# dcdc_60v_12v.net
KiCad netlist of a schematic drawn in Altium Designer
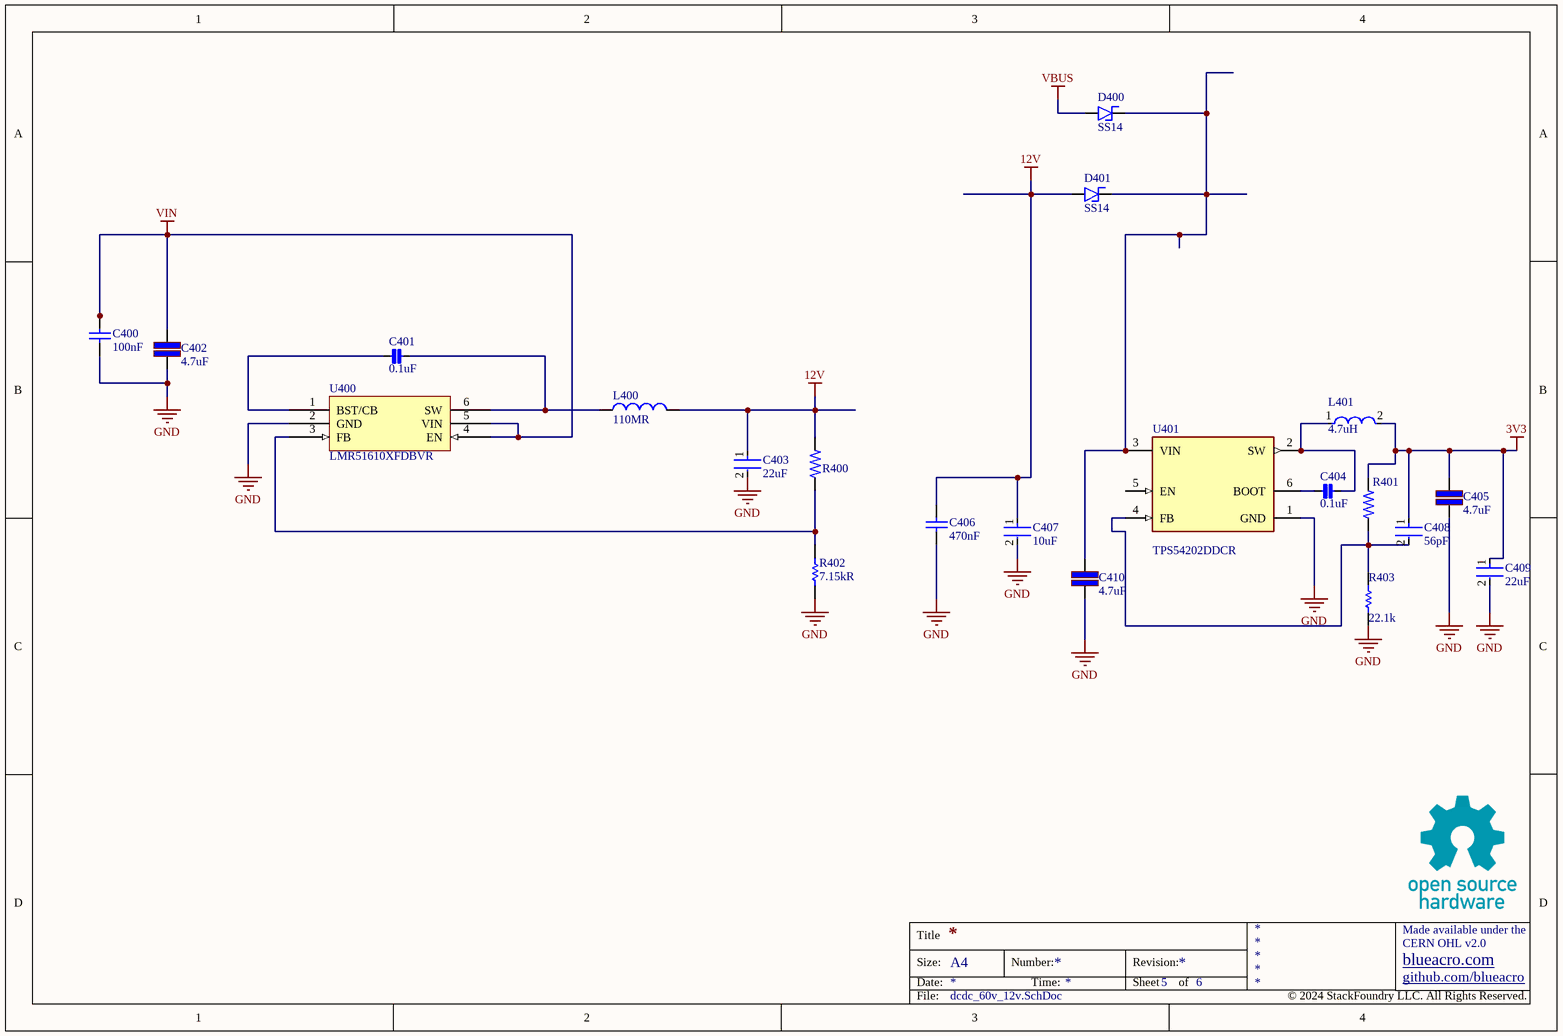
[diagram p0: dcdc_60v_12v.SchDoc]

(export (version "E")
  (design (tool "Eeschema 10.0.6"))
  (components
    (comp (ref "C400")
      (value "100nF")
      (footprint "CAPC2013X94X50ML20T25")
      (fields (field (name "Comment") "0.1uF X7R 100V 0805"))
      (libsource (lib "StackFoundry LLC") (part "CAP"))
    )
    (comp (ref "C401")
      (value "0.1uF")
      (footprint "FP-CL10-IPC_B")
      (description "Cap Ceramic 0.1uF 50V X7R 20% SMD 0603 125C Paper T/R")
      (fields (field (name "VOLTAGE") "50V") (field (name "Comment") "CAP 0.1uF 50V X7R 0603"))
      (libsource (lib "StackFoundry LLC") (part "C-EU"))
    )
    (comp (ref "C402")
      (value "4.7uF")
      (footprint "CAPC3225X20N")
      (description "CAP CER 4.7UF 50V X7R 1210")
      (fields (field (name "VOLTAGE") "50V") (field (name "TOLERANCE") "10%"))
      (libsource (lib "StackFoundry LLC") (part "4.7uF"))
    )
    (comp (ref "C403")
      (value "22uF")
      (footprint "FP-1210-L_3_2_0_3-W_2_5_0-MFG")
      (description "1210 22 uF 25 V ±20% Tolerance X7R Multilayer Ceramic Chip Capacitor")
      (fields (field (name "TOLERANCE") "20%") (field (name "Comment") "CAP 22uF 25V 1210 X7R"))
      (libsource (lib "StackFoundry LLC") (part "02cd4be3c70576c341d710602a673aa"))
    )
    (comp (ref "C404")
      (value "0.1uF")
      (footprint "FP-CL10-IPC_B")
      (description "Cap Ceramic 0.1uF 50V X7R 20% SMD 0603 125C Paper T/R")
      (fields (field (name "VOLTAGE") "50V") (field (name "Comment") "CAP 0.1uF 50V X7R 0603"))
      (libsource (lib "StackFoundry LLC") (part "C-EU"))
    )
    (comp (ref "C405")
      (value "4.7uF")
      (footprint "CAPC3225X20N")
      (description "CAP CER 4.7UF 50V X7R 1210")
      (fields (field (name "VOLTAGE") "50V") (field (name "TOLERANCE") "10%"))
      (libsource (lib "StackFoundry LLC") (part "4.7uF"))
    )
    (comp (ref "C406")
      (value "470nF")
      (footprint "CAPC1210(3225)230_M")
      (description "Multilayer Ceramic Capacitor, 0.47 uF, 50 V, ± 10%, X7R, 1210 [3225 Metric]")
      (fields (field (name "TOLERANCE") "10%") (field (name "VOLTAGE") "50V"))
      (libsource (lib "StackFoundry LLC") (part "CAP"))
    )
    (comp (ref "C407")
      (value "10uF")
      (footprint "FP-GRM32E-0_2-0_3-MFG")
      (description "Multilayer Ceramic Capacitors MLCC - SMD/SMT 1210 10uF 63volts *Derate Voltage/Temp")
      (fields (field (name "TOLERANCE") "10%") (field (name "VOLTAGE") "63V"))
      (libsource (lib "StackFoundry LLC") (part "11868f565c42a9108669ba33697ecf6"))
    )
    (comp (ref "C408")
      (value "56pF")
      (footprint "FP-C0603C-CF-IPC_B")
      (description "Multilayer Ceramic Capacitor, 56 pF, 50 V, ± 5%, C0G (NP0), 0603 [1608 Metric]")
      (fields (field (name "TOLERANCE") "5%") (field (name "Comment") "C0603C560J5GACTU"))
      (libsource (lib "StackFoundry LLC") (part "b4654b650e69147ec39a6b967a45e02"))
    )
    (comp (ref "C409")
      (value "22uF")
      (footprint "FP-1210-L_3_2_0_3-W_2_5_0-MFG")
      (description "1210 22 uF 25 V ±20% Tolerance X7R Multilayer Ceramic Chip Capacitor")
      (fields (field (name "TOLERANCE") "20%") (field (name "Comment") "CAP 22uF 25V 1210 X7R"))
      (libsource (lib "StackFoundry LLC") (part "02cd4be3c70576c341d710602a673aa"))
    )
    (comp (ref "C410")
      (value "4.7uF")
      (footprint "CAPC3225X20N")
      (description "CAP CER 4.7UF 50V X7R 1210")
      (fields (field (name "VOLTAGE") "50V") (field (name "TOLERANCE") "10%"))
      (libsource (lib "StackFoundry LLC") (part "4.7uF"))
    )
    (comp (ref "D400")
      (value "SS14")
      (footprint "SMA")
      (libsource (lib "StackFoundry LLC") (part "DIODE_SCHOTTKY"))
    )
    (comp (ref "D401")
      (value "SS14")
      (footprint "SMA")
      (libsource (lib "StackFoundry LLC") (part "DIODE_SCHOTTKY"))
    )
    (comp (ref "L400")
      (value "110MR")
      (footprint "SRR1260-680M-Footprint-1")
      (description "Ind Power Shielded Wirewound 68uH 20% 100KHz 22Q-Factor Ferrite 2.1A T/R")
      (fields (field (name "TOLERANCE") "20%") (field (name "Comment") "SRR1260-680M"))
      (libsource (lib "StackFoundry LLC") (part "L-US"))
    )
    (comp (ref "L401")
      (value "4.7uH")
      (footprint "FP-SRN4018-MFG")
      (description "Ind Power Semi-Shielded Wirewound 4.7uH 20% 100KHz Ferrite 1.9A 1515 T/R")
      (fields (field (name "TOLERANCE") "20%") (field (name "Comment") "SRN4018-4R7M"))
      (libsource (lib "StackFoundry LLC") (part "725321dda6339637d4d059423bc1c3c"))
    )
    (comp (ref "R400")
      (value "100k 0603 1%")
      (footprint "RESC1608-IPC-LL")
      (description "Res Thick Film 1.6 x 0.8 mm 100K Ohm 1% 0.1W(1/10W) 100ppm/ C Molded SMD Paper T/R")
      (libsource (lib "StackFoundry LLC") (part "R-US"))
    )
    (comp (ref "R401")
      (value "100k 0603 1%")
      (footprint "RESC1608-IPC-LL")
      (description "Res Thick Film 1.6 x 0.8 mm 100K Ohm 1% 0.1W(1/10W) 100ppm/ C Molded SMD Paper T/R")
      (libsource (lib "StackFoundry LLC") (part "R-US"))
    )
    (comp (ref "R402")
      (value "7.15kR")
      (footprint "RESC1608X55X30NL20T20")
      (description "Res Thin Film 0603 7.15K Ohm 0.1% 1/10W ±25ppm/°C Molded SMD SMD Punched Carrier T/R")
      (fields (field (name "Comment") "7.15k 0603 0.1%"))
      (libsource (lib "StackFoundry LLC") (part "RES"))
    )
    (comp (ref "R403")
      (value "22.1k")
      (footprint "RESC1608-IPC-LL")
      (description "RES SMD 22.1KOHM 0.1% 1/10W 0603")
      (fields (field (name "Comment") "22.1k 0603 0.1%"))
      (libsource (lib "StackFoundry LLC") (part "RES"))
    )
    (comp (ref "U400")
      (value "LMR51610XFDBVR")
      (footprint "SOT95P280X145-6N")
      (libsource (lib "StackFoundry LLC") (part "LMR51610XFDBVR-Symbol-1"))
    )
    (comp (ref "U401")
      (value "TPS54202DDCR")
      (footprint "FP-DDC0006A-IPC_C")
      (libsource (lib "StackFoundry LLC") (part "35c2d3f1afc239a386b2ba50eead654"))
    )
  )
  (nets
    (net (code "1") (name "3V3") (class "Default")
      (node (ref "C405") (pin "2") (pintype "passive"))
      (node (ref "C408") (pin "1") (pinfunction "1_1") (pintype "passive"))
      (node (ref "C409") (pin "1") (pinfunction "1_1") (pintype "passive"))
      (node (ref "L401") (pin "2") (pinfunction "2_2") (pintype "passive"))
      (node (ref "R401") (pin "2") (pinfunction "2_2") (pintype "passive"))
    )
    (net (code "2") (name "12V") (class "Default")
      (node (ref "C403") (pin "1") (pinfunction "1_1") (pintype "passive"))
      (node (ref "C406") (pin "2") (pinfunction "2_2") (pintype "passive"))
      (node (ref "C407") (pin "1") (pinfunction "1_1") (pintype "passive"))
      (node (ref "D401") (pin "A") (pinfunction "A_A") (pintype "power_in"))
      (node (ref "L400") (pin "2") (pinfunction "2_2") (pintype "passive"))
      (node (ref "R400") (pin "2") (pinfunction "2_2") (pintype "passive"))
    )
    (net (code "3") (name "GND") (class "Default")
      (node (ref "C400") (pin "1") (pinfunction "1_1") (pintype "passive"))
      (node (ref "C402") (pin "1") (pintype "passive"))
      (node (ref "C403") (pin "2") (pinfunction "2_2") (pintype "passive"))
      (node (ref "C405") (pin "1") (pintype "passive"))
      (node (ref "C406") (pin "1") (pinfunction "1_1") (pintype "passive"))
      (node (ref "C407") (pin "2") (pinfunction "2_2") (pintype "passive"))
      (node (ref "C409") (pin "2") (pinfunction "2_2") (pintype "passive"))
      (node (ref "C410") (pin "1") (pintype "passive"))
      (node (ref "R402") (pin "1") (pinfunction "1_1") (pintype "passive"))
      (node (ref "R403") (pin "1") (pinfunction "1_1") (pintype "passive"))
      (node (ref "U400") (pin "2") (pinfunction "GND_2") (pintype "power_in"))
      (node (ref "U401") (pin "1") (pinfunction "GND_1") (pintype "power_in"))
    )
    (net (code "4") (name "Net-(U400-BST{slash}CB)") (class "Default")
      (node (ref "C401") (pin "1") (pinfunction "1_1") (pintype "passive"))
      (node (ref "U400") (pin "1") (pinfunction "BST/CB_1") (pintype "passive"))
    )
    (net (code "5") (name "Net-(U400-FB)") (class "Default")
      (node (ref "R400") (pin "1") (pinfunction "1_1") (pintype "passive"))
      (node (ref "R402") (pin "2") (pinfunction "2_2") (pintype "passive"))
      (node (ref "U400") (pin "3") (pinfunction "FB_3") (pintype "input"))
    )
    (net (code "6") (name "Net-(U400-SW)") (class "Default")
      (node (ref "C401") (pin "2") (pinfunction "2_2") (pintype "passive"))
      (node (ref "L400") (pin "1") (pinfunction "1_1") (pintype "passive"))
      (node (ref "U400") (pin "6") (pinfunction "SW_6") (pintype "passive"))
    )
    (net (code "7") (name "Net-(U401-BOOT)") (class "Default")
      (node (ref "C404") (pin "1") (pinfunction "1_1") (pintype "passive"))
      (node (ref "U401") (pin "6") (pinfunction "BOOT_6") (pintype "passive"))
    )
    (net (code "8") (name "Net-(U401-FB)") (class "Default")
      (node (ref "C408") (pin "2") (pinfunction "2_2") (pintype "passive"))
      (node (ref "R401") (pin "1") (pinfunction "1_1") (pintype "passive"))
      (node (ref "R403") (pin "2") (pinfunction "2_2") (pintype "passive"))
      (node (ref "U401") (pin "4") (pinfunction "FB_4") (pintype "input"))
    )
    (net (code "9") (name "Net-(U401-SW)") (class "Default")
      (node (ref "C404") (pin "2") (pinfunction "2_2") (pintype "passive"))
      (node (ref "L401") (pin "1") (pinfunction "1_1") (pintype "passive"))
      (node (ref "U401") (pin "2") (pinfunction "SW_2") (pintype "output"))
    )
    (net (code "10") (name "Net-(U401-VIN)") (class "Default")
      (node (ref "C410") (pin "2") (pintype "passive"))
      (node (ref "D400") (pin "K") (pinfunction "K_K") (pintype "power_in"))
      (node (ref "D401") (pin "K") (pinfunction "K_K") (pintype "power_in"))
      (node (ref "U401") (pin "3") (pinfunction "VIN_3") (pintype "power_in"))
    )
    (net (code "11") (name "VBUS") (class "Default")
      (node (ref "D400") (pin "A") (pinfunction "A_A") (pintype "power_in"))
    )
    (net (code "12") (name "VIN") (class "Default")
      (node (ref "C400") (pin "2") (pinfunction "2_2") (pintype "passive"))
      (node (ref "C402") (pin "2") (pintype "passive"))
      (node (ref "U400") (pin "4") (pinfunction "EN_4") (pintype "input"))
      (node (ref "U400") (pin "5") (pinfunction "VIN_5") (pintype "power_in"))
    )
    (net (code "13") (name "unconnected-(U401-EN-Pad5)") (class "Default")
      (node (ref "U401") (pin "5") (pinfunction "EN_5") (pintype "input"))
    )
  )
)
